# CPU-board-Sheet1-multi.net
KiCad netlist of a schematic drawn in Altium Designer
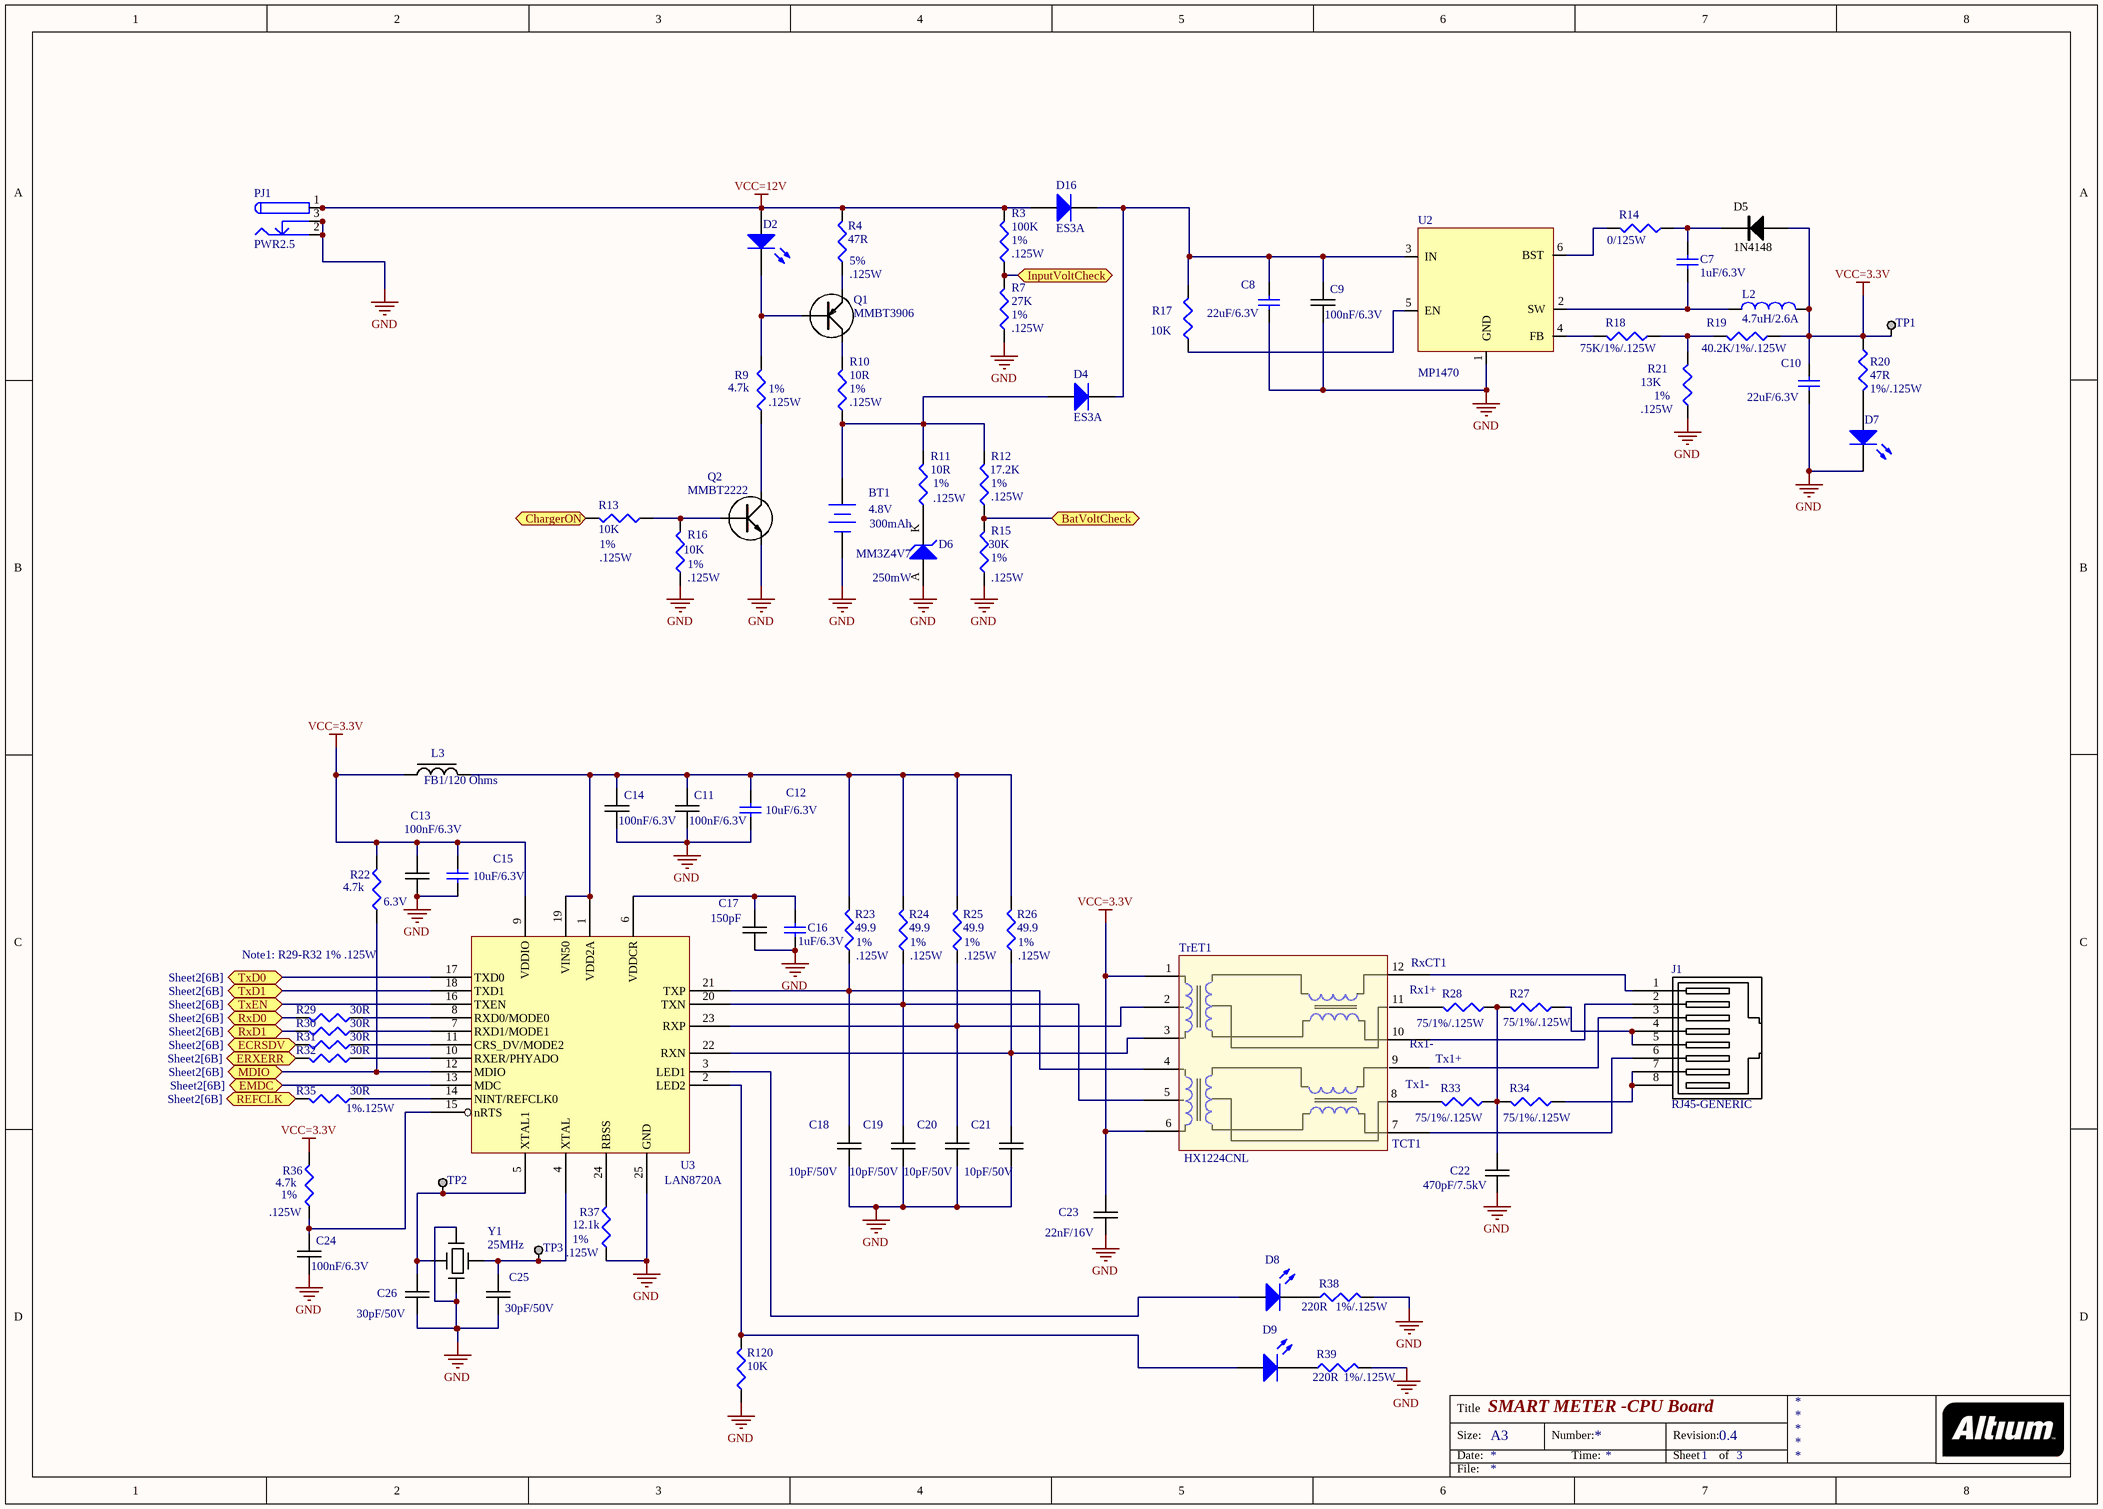
[diagram p0: CPU-board-Sheet1-multi.SchDoc]

(export (version "E")
  (design (tool "Eeschema 10.0.6"))
  (components
    (comp (ref "BT1")
      (value "4.8V")
      (footprint "BAT-2")
      (description "Multicell Battery")
      (fields
        (field (name "MANUFACTURER") "Guangdong, China (Mainland)")
        (field (name "PUBLISHER") "sunbangpower.en.alibaba.com")
      )
      (libsource (lib "Miscellaneous Devices") (part "Battery"))
    )
    (comp (ref "C7")
      (value "1uF/6.3V")
      (footprint "0402C-GENERIC")
      (description "Capacitor")
      (fields (field (name "MANUFACTURER") "Murata") (field (name "PUBLISHER") "Altium Limited"))
      (libsource (lib "Miscellaneous Devices") (part "Cap"))
    )
    (comp (ref "C8")
      (value "22uF/6.3V")
      (footprint "1206C-GENERIC")
      (description "Capacitor")
      (fields (field (name "MANUFACTURER") "Murata") (field (name "PUBLISHER") "Altium Limited"))
      (libsource (lib "Miscellaneous Devices") (part "Cap"))
    )
    (comp (ref "C9")
      (value "100nF/6.3V")
      (footprint "0402C-GENERIC")
      (description "CAPACITOR 0805 CERAMIC")
      (fields (field (name "MANUFACTURER") "Taiyo Yuden"))
      (libsource (lib "vh_altium_library") (part "0805C-18PF-50V-C0G-JOH"))
    )
    (comp (ref "C10")
      (value "22uF/6.3V")
      (footprint "1206C-GENERIC")
      (description "Capacitor")
      (fields (field (name "MANUFACTURER") "Murata") (field (name "PUBLISHER") "Altium Limited"))
      (libsource (lib "Miscellaneous Devices") (part "Cap"))
    )
    (comp (ref "C11")
      (value "100nF/6.3V")
      (footprint "0402C-GENERIC")
      (description "CAPACITOR 0805 CERAMIC")
      (fields (field (name "MANUFACTURER") "Taiyo Yuden"))
      (libsource (lib "vh_altium_library") (part "0805C-18PF-50V-C0G-JOH"))
    )
    (comp (ref "C12")
      (value "10uF/6.3V")
      (footprint "0402C-GENERIC")
      (description "Capacitor")
      (fields (field (name "MANUFACTURER") "Murata") (field (name "PUBLISHER") "Altium Limited"))
      (libsource (lib "Miscellaneous Devices") (part "Cap"))
    )
    (comp (ref "C13")
      (value "100nF/6.3V")
      (footprint "0402C-GENERIC")
      (description "CAPACITOR 0805 CERAMIC")
      (fields (field (name "MANUFACTURER") "Taiyo Yuden"))
      (libsource (lib "vh_altium_library") (part "0805C-18PF-50V-C0G-JOH"))
    )
    (comp (ref "C14")
      (value "100nF/6.3V")
      (footprint "0402C-GENERIC")
      (description "CAPACITOR 0805 CERAMIC")
      (fields (field (name "MANUFACTURER") "Taiyo Yuden"))
      (libsource (lib "vh_altium_library") (part "0805C-18PF-50V-C0G-JOH"))
    )
    (comp (ref "C15")
      (value "10uF/6.3V")
      (footprint "0402C-GENERIC")
      (description "Capacitor")
      (fields (field (name "MANUFACTURER") "Murata") (field (name "PUBLISHER") "Altium Limited"))
      (libsource (lib "Miscellaneous Devices") (part "Cap"))
    )
    (comp (ref "C16")
      (value "1uF/6.3V")
      (footprint "0402C-GENERIC")
      (description "Capacitor")
      (fields (field (name "MANUFACTURER") "Murata") (field (name "PUBLISHER") "Altium Limited"))
      (libsource (lib "Miscellaneous Devices") (part "Cap"))
    )
    (comp (ref "C17")
      (value "150pF")
      (footprint "0402C-GENERIC")
      (description "CAPACITOR 0805 CERAMIC")
      (fields (field (name "MANUFACTURER") "Wurth Electronics"))
      (libsource (lib "vh_altium_library") (part "0805C-18PF-50V-C0G-JOH"))
    )
    (comp (ref "C18")
      (value "10pF/50V")
      (footprint "0402C-GENERIC")
      (description "CAPACITOR 0805 CERAMIC")
      (fields (field (name "MANUFACTURER") "Murata"))
      (libsource (lib "vh_altium_library") (part "0805C-18PF-50V-C0G-JOH"))
    )
    (comp (ref "C19")
      (value "10pF/50V")
      (footprint "0402C-GENERIC")
      (description "CAPACITOR 0805 CERAMIC")
      (fields (field (name "MANUFACTURER") "Murata"))
      (libsource (lib "vh_altium_library") (part "0805C-18PF-50V-C0G-JOH"))
    )
    (comp (ref "C20")
      (value "10pF/50V")
      (footprint "0402C-GENERIC")
      (description "CAPACITOR 0805 CERAMIC")
      (fields (field (name "MANUFACTURER") "Murata"))
      (libsource (lib "vh_altium_library") (part "0805C-18PF-50V-C0G-JOH"))
    )
    (comp (ref "C21")
      (value "10pF/50V")
      (footprint "0402C-GENERIC")
      (description "CAPACITOR 0805 CERAMIC")
      (fields (field (name "MANUFACTURER") "Murata"))
      (libsource (lib "vh_altium_library") (part "0805C-18PF-50V-C0G-JOH"))
    )
    (comp (ref "C22")
      (value "470pF/7.5kV")
      (footprint "1808")
      (description "CAPACITOR 1808CERAMIC")
      (fields (field (name "MANUFACTURER") "Murata"))
      (libsource (lib "vh_altium_library") (part "0805C-18PF-50V-C0G-JOH"))
    )
    (comp (ref "C23")
      (value "22nF/16V")
      (footprint "0402C-GENERIC")
      (description "CAPACITOR 0805 CERAMIC")
      (fields (field (name "MANUFACTURER") "Murata Electronics"))
      (libsource (lib "vh_altium_library") (part "0805C-18PF-50V-C0G-JOH"))
    )
    (comp (ref "C24")
      (value "100nF/6.3V")
      (footprint "0402C-GENERIC")
      (description "CAPACITOR 0805 CERAMIC")
      (fields (field (name "MANUFACTURER") "Taiyo Yuden"))
      (libsource (lib "vh_altium_library") (part "0805C-18PF-50V-C0G-JOH"))
    )
    (comp (ref "C25")
      (value "30pF/50V")
      (footprint "0402C-GENERIC")
      (description "CAPACITOR 0805 CERAMIC")
      (fields (field (name "MANUFACTURER") "Murata"))
      (libsource (lib "vh_altium_library") (part "0805C-18PF-50V-C0G-JOH"))
    )
    (comp (ref "C26")
      (value "30pF/50V")
      (footprint "0402C-GENERIC")
      (description "CAPACITOR 0805 CERAMIC")
      (fields (field (name "MANUFACTURER") "Murata"))
      (libsource (lib "vh_altium_library") (part "0805C-18PF-50V-C0G-JOH"))
    )
    (comp (ref "D2")
      (value "LED2")
      (footprint "LED-SM")
      (description "Typical RED, GREEN, YELLOW, AMBER GaAs LED")
      (fields (field (name "MANUFACTURER") "Lite-On Inc") (field (name "PUBLISHER") "Altium Limited"))
      (libsource (lib "Miscellaneous Devices") (part "LED2"))
    )
    (comp (ref "D4")
      (value "ES3A")
      (footprint "DO214AA")
      (description "1 Amp General Purpose Rectifier")
      (fields (field (name "MANUFACTURER") "Fairchild Co") (field (name "PUBLISHER") "Altium Limited"))
      (libsource (lib "Miscellaneous Devices") (part "Diode 1N4007"))
    )
    (comp (ref "D5")
      (value "1N4148")
      (footprint "SOD-123")
      (description "1N4001")
      (fields (field (name "MANUFACTURER") "Vishay"))
      (libsource (lib "vh_altium_library") (part "1N4001"))
    )
    (comp (ref "D6")
      (value "MM3Z4V7")
      (footprint "SOT23-DIODE")
      (description "Zener Diode")
      (fields (field (name "MANUFACTURER") "Fairchild Semi") (field (name "PUBLISHER") "Altium Limited"))
      (libsource (lib "Miscellaneous Devices") (part "D Zener"))
    )
    (comp (ref "D7")
      (value "LED2")
      (footprint "LED-SM")
      (description "Typical RED, GREEN, YELLOW, AMBER GaAs LED")
      (fields (field (name "MANUFACTURER") "Lite-On Inc") (field (name "PUBLISHER") "Altium Limited"))
      (libsource (lib "Miscellaneous Devices") (part "LED2"))
    )
    (comp (ref "D8")
      (value "LED2")
      (footprint "LED-SM")
      (description "Typical RED, GREEN, YELLOW, AMBER GaAs LED")
      (fields (field (name "MANUFACTURER") "Lite-On Inc") (field (name "PUBLISHER") "Altium Limited"))
      (libsource (lib "Miscellaneous Devices") (part "LED2"))
    )
    (comp (ref "D9")
      (value "LED2")
      (footprint "LED-SM")
      (description "Typical RED, GREEN, YELLOW, AMBER GaAs LED")
      (fields (field (name "MANUFACTURER") "Lite-On Inc") (field (name "PUBLISHER") "Altium Limited"))
      (libsource (lib "Miscellaneous Devices") (part "LED2"))
    )
    (comp (ref "D16")
      (value "ES3A")
      (footprint "DO214AA")
      (description "1 Amp General Purpose Rectifier")
      (fields (field (name "MANUFACTURER") "Fairchild Co") (field (name "PUBLISHER") "Altium Limited"))
      (libsource (lib "Miscellaneous Devices") (part "Diode 1N4007"))
    )
    (comp (ref "J1")
      (value "RJ45-GENERIC")
      (footprint "RJ45-8/8")
      (description "GENERIC RJ45 CONNECTOR 8 PIN")
      (fields (field (name "MANUFACTURER") "Assman WSW Components"))
      (libsource (lib "vh_altium_library") (part "RJ45-GENERIC"))
    )
    (comp (ref "L2")
      (value "4.7uH/2.6A")
      (footprint "Inductor 4.7/6.8")
      (description "Inductor")
      (fields (field (name "MANUFACTURER") "Bourns") (field (name "PUBLISHER") "Altium Limited"))
      (libsource (lib "Miscellaneous Devices") (part "Inductor"))
    )
    (comp (ref "L3")
      (value "FB1/120 Ohms")
      (footprint "0603C-2U2")
      (description "1239AS-H-1R0N")
      (fields (field (name "MANUFACTURER") "Murata Electronics"))
      (libsource (lib "SMD Magnetics-SM") (part "1U-1239AS-TOKO"))
    )
    (comp (ref "PJ1")
      (value "PWR2.5")
      (footprint "Female Plug")
      (description "Low Voltage Power Supply Connector")
      (fields (field (name "MANUFACTURER") "CUI Inc") (field (name "PUBLISHER") "Altium Limited"))
      (libsource (lib "Miscellaneous Connectors") (part "PWR2.5"))
    )
    (comp (ref "Q1")
      (value "MMBT3906")
      (footprint "SOT23-BCE")
      (description "GENERIC PNP BIPOLAR TRANSISTOR")
      (fields (field (name "MANUFACTURER") "On Semi"))
      (libsource (lib "generic") (part "PNP-GENERIC"))
    )
    (comp (ref "Q2")
      (value "MMBT2222")
      (footprint "MMBT2222")
      (description "BC847 SMALL SIGNAL NPN TRANSISTOR")
      (fields (field (name "MANUFACTURER") "Diodes  Inc."))
      (libsource (lib "vh_altium_library") (part "MMBT2222"))
    )
    (comp (ref "R3")
      (value "100K")
      (footprint "0402R-TBD")
      (description "Resistor")
      (fields (field (name "MANUFACTURER") "Panasonic") (field (name "PUBLISHER") "Altium Limited"))
      (libsource (lib "Miscellaneous Devices") (part "Res3"))
    )
    (comp (ref "R4")
      (value "47R")
      (footprint "0402R-TBD")
      (description "Resistor")
      (fields (field (name "PUBLISHER") "Altium Limited"))
      (libsource (lib "Miscellaneous Devices") (part "Res3"))
    )
    (comp (ref "R7")
      (value "27K")
      (footprint "0402R-TBD")
      (description "Resistor")
      (fields (field (name "MANUFACTURER") "Panasonic") (field (name "PUBLISHER") "Altium Limited"))
      (libsource (lib "Miscellaneous Devices") (part "Res3"))
    )
    (comp (ref "R9")
      (value "4.7k")
      (footprint "0402R-TBD")
      (description "Resistor")
      (fields (field (name "MANUFACTURER") "Panasonic") (field (name "PUBLISHER") "Altium Limited"))
      (libsource (lib "Miscellaneous Devices") (part "Res3"))
    )
    (comp (ref "R10")
      (value "10R")
      (footprint "0402R-TBD")
      (description "Resistor")
      (fields (field (name "MANUFACTURER") "Panasonic") (field (name "PUBLISHER") "Altium Limited"))
      (libsource (lib "Miscellaneous Devices") (part "Res3"))
    )
    (comp (ref "R11")
      (value "10R")
      (footprint "0402R-TBD")
      (description "Resistor")
      (fields (field (name "MANUFACTURER") "Panasonic") (field (name "PUBLISHER") "Altium Limited"))
      (libsource (lib "Miscellaneous Devices") (part "Res3"))
    )
    (comp (ref "R12")
      (value "17.2K")
      (footprint "0402R-TBD")
      (description "Resistor")
      (fields (field (name "MANUFACTURER") "Vishay Dale") (field (name "PUBLISHER") "Altium Limited"))
      (libsource (lib "Miscellaneous Devices") (part "Res3"))
    )
    (comp (ref "R13")
      (value "10K")
      (footprint "0402R-TBD")
      (description "Resistor")
      (fields (field (name "MANUFACTURER") "Panasonic") (field (name "PUBLISHER") "Altium Limited"))
      (libsource (lib "Miscellaneous Devices") (part "Res3"))
    )
    (comp (ref "R14")
      (value "0/125W")
      (footprint "0402C-GENERIC")
      (description "Resistor")
      (fields (field (name "MANUFACTURER") "Vishay Dale") (field (name "PUBLISHER") "Altium Limited"))
      (libsource (lib "Miscellaneous Devices") (part "Res3"))
    )
    (comp (ref "R15")
      (value "30K")
      (footprint "0402R-TBD")
      (description "Resistor")
      (fields (field (name "MANUFACTURER") "Panasonic") (field (name "PUBLISHER") "Altium Limited"))
      (libsource (lib "Miscellaneous Devices") (part "Res3"))
    )
    (comp (ref "R16")
      (value "10K")
      (footprint "0402R-TBD")
      (description "Resistor")
      (fields (field (name "MANUFACTURER") "Panasonic") (field (name "PUBLISHER") "Altium Limited"))
      (libsource (lib "Miscellaneous Devices") (part "Res3"))
    )
    (comp (ref "R17")
      (value "10K")
      (footprint "0402R-TBD")
      (description "Resistor")
      (fields (field (name "MANUFACTURER") "Panasonic") (field (name "PUBLISHER") "Altium Limited"))
      (libsource (lib "Miscellaneous Devices") (part "Res3"))
    )
    (comp (ref "R18")
      (value "75K/1%/.125W")
      (footprint "0402C-TBD")
      (description "Resistor")
      (fields (field (name "MANUFACTURER") "Panasonic") (field (name "PUBLISHER") "Altium Limited"))
      (libsource (lib "Miscellaneous Devices") (part "Res3"))
    )
    (comp (ref "R19")
      (value "40.2K/1%/.125W")
      (footprint "0402R-TBD")
      (description "Resistor")
      (fields (field (name "MANUFACTURER") "Panasonic") (field (name "PUBLISHER") "Altium Limited"))
      (libsource (lib "Miscellaneous Devices") (part "Res3"))
    )
    (comp (ref "R20")
      (value "47R")
      (footprint "0402R-TBD")
      (description "Resistor")
      (fields (field (name "PUBLISHER") "Altium Limited"))
      (libsource (lib "Miscellaneous Devices") (part "Res3"))
    )
    (comp (ref "R21")
      (value "13K")
      (footprint "0402R-TBD")
      (description "Resistor")
      (fields (field (name "MANUFACTURER") "Panasonic") (field (name "PUBLISHER") "Altium Limited"))
      (libsource (lib "Miscellaneous Devices") (part "Res3"))
    )
    (comp (ref "R22")
      (value "4.7k")
      (footprint "0402R-TBD")
      (description "Resistor")
      (fields (field (name "MANUFACTURER") "Panasonic") (field (name "PUBLISHER") "Altium Limited"))
      (libsource (lib "Miscellaneous Devices") (part "Res3"))
    )
    (comp (ref "R23")
      (value "49.9")
      (footprint "0402R-TBD")
      (description "Resistor")
      (fields (field (name "MANUFACTURER") "Panasonic") (field (name "PUBLISHER") "Altium Limited"))
      (libsource (lib "Miscellaneous Devices") (part "Res3"))
    )
    (comp (ref "R24")
      (value "49.9")
      (footprint "0402R-TBD")
      (description "Resistor")
      (fields (field (name "MANUFACTURER") "Panasonic") (field (name "PUBLISHER") "Altium Limited"))
      (libsource (lib "Miscellaneous Devices") (part "Res3"))
    )
    (comp (ref "R25")
      (value "49.9")
      (footprint "0402R-TBD")
      (description "Resistor")
      (fields (field (name "MANUFACTURER") "Panasonic") (field (name "PUBLISHER") "Altium Limited"))
      (libsource (lib "Miscellaneous Devices") (part "Res3"))
    )
    (comp (ref "R26")
      (value "49.9")
      (footprint "0402R-TBD")
      (description "Resistor")
      (fields (field (name "MANUFACTURER") "Panasonic") (field (name "PUBLISHER") "Altium Limited"))
      (libsource (lib "Miscellaneous Devices") (part "Res3"))
    )
    (comp (ref "R27")
      (value "75/1%/.125W")
      (footprint "0402R-TBD")
      (description "Resistor")
      (fields (field (name "MANUFACTURER") "Panasonic") (field (name "PUBLISHER") "Altium Limited"))
      (libsource (lib "Miscellaneous Devices") (part "Res3"))
    )
    (comp (ref "R28")
      (value "75/1%/.125W")
      (footprint "0402R-TBD")
      (description "Resistor")
      (fields (field (name "MANUFACTURER") "Panasonic") (field (name "PUBLISHER") "Altium Limited"))
      (libsource (lib "Miscellaneous Devices") (part "Res3"))
    )
    (comp (ref "R29")
      (value "30R")
      (footprint "0402R-TBD")
      (description "Resistor")
      (fields (field (name "MANUFACTURER") "Panasonic") (field (name "PUBLISHER") "Altium Limited"))
      (libsource (lib "Miscellaneous Devices") (part "Res3"))
    )
    (comp (ref "R30")
      (value "30R")
      (footprint "0402R-TBD")
      (description "Resistor")
      (fields (field (name "MANUFACTURER") "Panasonic") (field (name "PUBLISHER") "Altium Limited"))
      (libsource (lib "Miscellaneous Devices") (part "Res3"))
    )
    (comp (ref "R31")
      (value "30R")
      (footprint "0402R-TBD")
      (description "Resistor")
      (fields (field (name "MANUFACTURER") "Panasonic") (field (name "PUBLISHER") "Altium Limited"))
      (libsource (lib "Miscellaneous Devices") (part "Res3"))
    )
    (comp (ref "R32")
      (value "30R")
      (footprint "0402R-TBD")
      (description "Resistor")
      (fields (field (name "MANUFACTURER") "Panasonic") (field (name "PUBLISHER") "Altium Limited"))
      (libsource (lib "Miscellaneous Devices") (part "Res3"))
    )
    (comp (ref "R33")
      (value "75/1%/.125W")
      (footprint "0402R-TBD")
      (description "Resistor")
      (fields (field (name "MANUFACTURER") "Panasonic") (field (name "PUBLISHER") "Altium Limited"))
      (libsource (lib "Miscellaneous Devices") (part "Res3"))
    )
    (comp (ref "R34")
      (value "75/1%/.125W")
      (footprint "0402R-TBD")
      (description "Resistor")
      (fields (field (name "MANUFACTURER") "Panasonic") (field (name "PUBLISHER") "Altium Limited"))
      (libsource (lib "Miscellaneous Devices") (part "Res3"))
    )
    (comp (ref "R35")
      (value "30R")
      (footprint "0402R-TBD")
      (description "Resistor")
      (fields (field (name "MANUFACTURER") "Panasonic") (field (name "PUBLISHER") "Altium Limited"))
      (libsource (lib "Miscellaneous Devices") (part "Res3"))
    )
    (comp (ref "R36")
      (value "4.7k")
      (footprint "0402R-TBD")
      (description "Resistor")
      (fields (field (name "MANUFACTURER") "Panasonic") (field (name "PUBLISHER") "Altium Limited"))
      (libsource (lib "Miscellaneous Devices") (part "Res3"))
    )
    (comp (ref "R37")
      (value "12.1k")
      (footprint "0402R-TBD")
      (description "Resistor")
      (fields (field (name "MANUFACTURER") "Panasonic") (field (name "PUBLISHER") "Altium Limited"))
      (libsource (lib "Miscellaneous Devices") (part "Res3"))
    )
    (comp (ref "R38")
      (value "220R")
      (footprint "0402R-TBD")
      (description "Resistor")
      (fields (field (name "MANUFACTURER") "Panasonic") (field (name "PUBLISHER") "Altium Limited"))
      (libsource (lib "Miscellaneous Devices") (part "Res3"))
    )
    (comp (ref "R39")
      (value "220R")
      (footprint "0402R-TBD")
      (description "Resistor")
      (fields (field (name "MANUFACTURER") "Panasonic") (field (name "PUBLISHER") "Altium Limited"))
      (libsource (lib "Miscellaneous Devices") (part "Res3"))
    )
    (comp (ref "R120")
      (value "10K")
      (footprint "0402R-TBD")
      (description "Resistor")
      (fields (field (name "MANUFACTURER") "Panasonic") (field (name "PUBLISHER") "Altium Limited"))
      (libsource (lib "Miscellaneous Devices") (part "Res3"))
    )
    (comp (ref "TP1")
      (value "TESTPOINT")
      (footprint "TESTPOINT")
      (description "TESTPOINT SCOPE GRABBER")
      (fields
        (field (name "MANUFACTURER PART NUMBER") "5010")
        (field (name "MANUFACTURER") "Keystone Electronics")
      )
      (libsource (lib "vh_altium_library") (part "TESTPOINT"))
    )
    (comp (ref "TP2")
      (value "TESTPOINT")
      (footprint "TESTPOINT")
      (description "TESTPOINT SCOPE GRABBER")
      (fields
        (field (name "MANUFACTURER PART NUMBER") "5010")
        (field (name "MANUFACTURER") "Keystone Electronics")
      )
      (libsource (lib "vh_altium_library") (part "TESTPOINT"))
    )
    (comp (ref "TP3")
      (value "TESTPOINT")
      (footprint "TESTPOINT")
      (description "TESTPOINT SCOPE GRABBER")
      (fields
        (field (name "MANUFACTURER PART NUMBER") "5010")
        (field (name "MANUFACTURER") "Keystone Electronics")
      )
      (libsource (lib "vh_altium_library") (part "TESTPOINT"))
    )
    (comp (ref "TrET1")
      (value "HX1224CNL")
      (footprint "HX1224-NL")
      (fields (field (name "MANUFACTURER") "Pulse Electronic Corporation"))
      (libsource (lib "SMLib") (part "hx1224nl"))
    )
    (comp (ref "U2")
      (value "MP1470")
      (footprint "MP1470")
      (fields (field (name "MANUFACTURER") "MPS Inc"))
      (libsource (lib "SMLib") (part "MP1470"))
    )
    (comp (ref "U3")
      (value "LAN8720A")
      (footprint "Atmel Multimedia:QFN24_4X4_N")
      (fields (field (name "MANUFACTURER") "Microchip"))
      (libsource (lib "SMLib") (part "LAN8720"))
    )
    (comp (ref "Y1")
      (value "25MHz")
      (footprint "CeramicResonator8-16MHZ")
      (description "25MHz CRYSTAL HC49US SHORT BODY")
      (fields (field (name "MANUFACTURER") "KDS DAISHINKU.Corp"))
      (libsource (lib "Crystals") (part "12MC-HC49US-7MM"))
    )
  )
  (nets
    (net (code "1") (name "/BatVoltCheck") (class "Default")
      (node (ref "R12") (pin "1") (pinfunction "1_1") (pintype "passive"))
      (node (ref "R15") (pin "2") (pinfunction "2_2") (pintype "passive"))
    )
    (net (code "2") (name "/ChargerON") (class "Default")
      (node (ref "R13") (pin "2") (pinfunction "2_2") (pintype "passive"))
    )
    (net (code "3") (name "/ECRSDV") (class "Default")
      (node (ref "R31") (pin "2") (pinfunction "2_2") (pintype "passive"))
    )
    (net (code "4") (name "/EMDC") (class "Default")
      (node (ref "U3") (pin "13") (pinfunction "MDC_13") (pintype "passive"))
    )
    (net (code "5") (name "/ERXERR") (class "Default")
      (node (ref "R32") (pin "2") (pinfunction "2_2") (pintype "passive"))
    )
    (net (code "6") (name "/InputVoltCheck") (class "Default")
      (node (ref "R3") (pin "1") (pinfunction "1_1") (pintype "passive"))
      (node (ref "R7") (pin "2") (pinfunction "2_2") (pintype "passive"))
    )
    (net (code "7") (name "/MDIO") (class "Default")
      (node (ref "R22") (pin "1") (pinfunction "1_1") (pintype "passive"))
      (node (ref "U3") (pin "12") (pinfunction "MDIO_12") (pintype "passive"))
    )
    (net (code "8") (name "/REFCLK") (class "Default")
      (node (ref "R35") (pin "2") (pinfunction "2_2") (pintype "passive"))
    )
    (net (code "9") (name "/RxD0") (class "Default")
      (node (ref "R29") (pin "2") (pinfunction "2_2") (pintype "passive"))
    )
    (net (code "10") (name "/RxD1") (class "Default")
      (node (ref "R30") (pin "2") (pinfunction "2_2") (pintype "passive"))
    )
    (net (code "11") (name "/TxD0") (class "Default")
      (node (ref "U3") (pin "17") (pinfunction "TXD0_17") (pintype "passive"))
    )
    (net (code "12") (name "/TxD1") (class "Default")
      (node (ref "U3") (pin "18") (pinfunction "TXD1_18") (pintype "passive"))
    )
    (net (code "13") (name "/TxEN") (class "Default")
      (node (ref "U3") (pin "16") (pinfunction "TXEN_16") (pintype "passive"))
    )
    (net (code "14") (name "GND") (class "Default")
      (node (ref "BT1") (pin "2") (pinfunction "-_2") (pintype "passive"))
      (node (ref "C10") (pin "2") (pinfunction "2_2") (pintype "passive"))
      (node (ref "C11") (pin "2") (pintype "passive"))
      (node (ref "C12") (pin "2") (pinfunction "2_2") (pintype "passive"))
      (node (ref "C13") (pin "2") (pintype "passive"))
      (node (ref "C14") (pin "2") (pintype "passive"))
      (node (ref "C15") (pin "2") (pinfunction "2_2") (pintype "passive"))
      (node (ref "C16") (pin "1") (pinfunction "1_1") (pintype "passive"))
      (node (ref "C17") (pin "2") (pintype "passive"))
      (node (ref "C18") (pin "2") (pintype "passive"))
      (node (ref "C19") (pin "2") (pintype "passive"))
      (node (ref "C20") (pin "2") (pintype "passive"))
      (node (ref "C21") (pin "2") (pintype "passive"))
      (node (ref "C22") (pin "2") (pintype "passive"))
      (node (ref "C23") (pin "2") (pintype "passive"))
      (node (ref "C24") (pin "2") (pintype "passive"))
      (node (ref "C25") (pin "2") (pintype "passive"))
      (node (ref "C26") (pin "2") (pintype "passive"))
      (node (ref "C8") (pin "2") (pinfunction "2_2") (pintype "passive"))
      (node (ref "C9") (pin "2") (pintype "passive"))
      (node (ref "D6") (pin "A") (pinfunction "A_A") (pintype "passive"))
      (node (ref "D7") (pin "2") (pinfunction "K_2") (pintype "passive"))
      (node (ref "PJ1") (pin "2") (pinfunction "2_2") (pintype "power_in"))
      (node (ref "PJ1") (pin "2A") (pinfunction "2A_2A") (pintype "power_in"))
      (node (ref "PJ1") (pin "2B") (pinfunction "2B_2B") (pintype "power_in"))
      (node (ref "PJ1") (pin "3") (pinfunction "3_3") (pintype "power_in"))
      (node (ref "PJ1") (pin "3A") (pinfunction "3A_3A") (pintype "power_in"))
      (node (ref "PJ1") (pin "3B") (pinfunction "3B_3B") (pintype "power_in"))
      (node (ref "Q2") (pin "E") (pintype "passive"))
      (node (ref "R120") (pin "1") (pinfunction "1_1") (pintype "passive"))
      (node (ref "R15") (pin "1") (pinfunction "1_1") (pintype "passive"))
      (node (ref "R16") (pin "1") (pinfunction "1_1") (pintype "passive"))
      (node (ref "R21") (pin "1") (pinfunction "1_1") (pintype "passive"))
      (node (ref "R37") (pin "1") (pinfunction "1_1") (pintype "passive"))
      (node (ref "R38") (pin "2") (pinfunction "2_2") (pintype "passive"))
      (node (ref "R39") (pin "2") (pinfunction "2_2") (pintype "passive"))
      (node (ref "R7") (pin "1") (pinfunction "1_1") (pintype "passive"))
      (node (ref "U2") (pin "1") (pinfunction "GND_1") (pintype "passive"))
      (node (ref "U3") (pin "25") (pinfunction "GND_25") (pintype "passive"))
      (node (ref "Y1") (pin "2") (pintype "passive"))
      (node (ref "Y1") (pin "4") (pintype "passive"))
    )
    (net (code "15") (name "Net-(BT1-+)") (class "Default")
      (node (ref "BT1") (pin "1") (pinfunction "+_1") (pintype "passive"))
      (node (ref "D4") (pin "1") (pinfunction "A_1") (pintype "passive"))
      (node (ref "R10") (pin "1") (pinfunction "1_1") (pintype "passive"))
      (node (ref "R11") (pin "2") (pinfunction "2_2") (pintype "passive"))
      (node (ref "R12") (pin "2") (pinfunction "2_2") (pintype "passive"))
    )
    (net (code "16") (name "Net-(C7-Pad2)") (class "Default")
      (node (ref "C7") (pin "2") (pinfunction "2_2") (pintype "passive"))
      (node (ref "D5") (pin "K") (pinfunction "K_K") (pintype "passive"))
      (node (ref "R14") (pin "1") (pinfunction "1_1") (pintype "passive"))
    )
    (net (code "17") (name "Net-(C22-Pad1)") (class "Default")
      (node (ref "C22") (pin "1") (pintype "passive"))
      (node (ref "R27") (pin "2") (pinfunction "2_2") (pintype "passive"))
      (node (ref "R28") (pin "1") (pinfunction "1_1") (pintype "passive"))
      (node (ref "R33") (pin "1") (pinfunction "1_1") (pintype "passive"))
      (node (ref "R34") (pin "2") (pinfunction "2_2") (pintype "passive"))
    )
    (net (code "18") (name "Net-(D2-K)") (class "Default")
      (node (ref "D2") (pin "2") (pinfunction "K_2") (pintype "passive"))
      (node (ref "Q1") (pin "B") (pintype "passive"))
      (node (ref "R9") (pin "2") (pinfunction "2_2") (pintype "passive"))
    )
    (net (code "19") (name "Net-(D6-PadK)") (class "Default")
      (node (ref "D6") (pin "K") (pinfunction "K_K") (pintype "passive"))
      (node (ref "R11") (pin "1") (pinfunction "1_1") (pintype "passive"))
    )
    (net (code "20") (name "Net-(D7-A)") (class "Default")
      (node (ref "D7") (pin "1") (pinfunction "A_1") (pintype "passive"))
      (node (ref "R20") (pin "2") (pinfunction "2_2") (pintype "passive"))
    )
    (net (code "21") (name "Net-(D8-A)") (class "Default")
      (node (ref "D8") (pin "1") (pinfunction "A_1") (pintype "passive"))
      (node (ref "U3") (pin "3") (pinfunction "LED1_3") (pintype "passive"))
    )
    (net (code "22") (name "Net-(D8-K)") (class "Default")
      (node (ref "D8") (pin "2") (pinfunction "K_2") (pintype "passive"))
      (node (ref "R38") (pin "1") (pinfunction "1_1") (pintype "passive"))
    )
    (net (code "23") (name "Net-(D9-A)") (class "Default")
      (node (ref "D9") (pin "1") (pinfunction "A_1") (pintype "passive"))
      (node (ref "R120") (pin "2") (pinfunction "2_2") (pintype "passive"))
      (node (ref "U3") (pin "2") (pinfunction "LED2_2") (pintype "passive"))
    )
    (net (code "24") (name "Net-(D9-K)") (class "Default")
      (node (ref "D9") (pin "2") (pinfunction "K_2") (pintype "passive"))
      (node (ref "R39") (pin "1") (pinfunction "1_1") (pintype "passive"))
    )
    (net (code "25") (name "Net-(D16-K)") (class "Default")
      (node (ref "C8") (pin "1") (pinfunction "1_1") (pintype "passive"))
      (node (ref "C9") (pin "1") (pintype "passive"))
      (node (ref "D16") (pin "2") (pinfunction "K_2") (pintype "passive"))
      (node (ref "D4") (pin "2") (pinfunction "K_2") (pintype "passive"))
      (node (ref "R17") (pin "2") (pinfunction "2_2") (pintype "passive"))
      (node (ref "U2") (pin "3") (pinfunction "IN_3") (pintype "passive"))
    )
    (net (code "26") (name "Net-(J1-Pad1)") (class "Default")
      (node (ref "J1") (pin "1") (pintype "passive"))
      (node (ref "TrET1") (pin "12") (pinfunction "12_12") (pintype "passive"))
    )
    (net (code "27") (name "Net-(J1-Pad2)") (class "Default")
      (node (ref "J1") (pin "2") (pintype "passive"))
      (node (ref "TrET1") (pin "10") (pinfunction "10_10") (pintype "passive"))
    )
    (net (code "28") (name "Net-(J1-Pad3)") (class "Default")
      (node (ref "J1") (pin "3") (pintype "passive"))
      (node (ref "TrET1") (pin "9") (pinfunction "9_9") (pintype "passive"))
    )
    (net (code "29") (name "Net-(J1-Pad4)") (class "Default")
      (node (ref "J1") (pin "4") (pintype "passive"))
      (node (ref "J1") (pin "5") (pintype "passive"))
      (node (ref "R27") (pin "1") (pinfunction "1_1") (pintype "passive"))
    )
    (net (code "30") (name "Net-(J1-Pad6)") (class "Default")
      (node (ref "J1") (pin "6") (pintype "passive"))
      (node (ref "TrET1") (pin "7") (pinfunction "7_7") (pintype "passive"))
    )
    (net (code "31") (name "Net-(J1-Pad7)") (class "Default")
      (node (ref "J1") (pin "7") (pintype "passive"))
      (node (ref "J1") (pin "8") (pintype "passive"))
      (node (ref "R34") (pin "1") (pinfunction "1_1") (pintype "passive"))
    )
    (net (code "32") (name "Net-(Q1-PadC)") (class "Default")
      (node (ref "Q1") (pin "C") (pintype "passive"))
      (node (ref "R10") (pin "2") (pinfunction "2_2") (pintype "passive"))
    )
    (net (code "33") (name "Net-(Q1-PadE)") (class "Default")
      (node (ref "Q1") (pin "E") (pintype "passive"))
      (node (ref "R4") (pin "1") (pinfunction "1_1") (pintype "passive"))
    )
    (net (code "34") (name "Net-(Q2-PadB)") (class "Default")
      (node (ref "Q2") (pin "B") (pintype "passive"))
      (node (ref "R13") (pin "1") (pinfunction "1_1") (pintype "passive"))
      (node (ref "R16") (pin "2") (pinfunction "2_2") (pintype "passive"))
    )
    (net (code "35") (name "Net-(Q2-PadC)") (class "Default")
      (node (ref "Q2") (pin "C") (pintype "passive"))
      (node (ref "R9") (pin "1") (pinfunction "1_1") (pintype "passive"))
    )
    (net (code "36") (name "Net-(R18-Pad1)") (class "Default")
      (node (ref "R18") (pin "1") (pinfunction "1_1") (pintype "passive"))
      (node (ref "R19") (pin "2") (pinfunction "2_2") (pintype "passive"))
      (node (ref "R21") (pin "2") (pinfunction "2_2") (pintype "passive"))
    )
    (net (code "37") (name "Net-(R28-Pad2)") (class "Default")
      (node (ref "R28") (pin "2") (pinfunction "2_2") (pintype "passive"))
      (node (ref "TrET1") (pin "11") (pinfunction "11_11") (pintype "passive"))
    )
    (net (code "38") (name "Net-(R33-Pad2)") (class "Default")
      (node (ref "R33") (pin "2") (pinfunction "2_2") (pintype "passive"))
      (node (ref "TrET1") (pin "8") (pinfunction "8_8") (pintype "passive"))
    )
    (net (code "39") (name "Net-(TrET1-TD-)") (class "Default")
      (node (ref "C21") (pin "1") (pintype "passive"))
      (node (ref "R26") (pin "1") (pinfunction "1_1") (pintype "passive"))
      (node (ref "TrET1") (pin "3") (pinfunction "TD-_3") (pintype "passive"))
      (node (ref "U3") (pin "22") (pinfunction "RXN_22") (pintype "passive"))
    )
    (net (code "40") (name "Net-(TrET1-TDCT)") (class "Default")
      (node (ref "C20") (pin "1") (pintype "passive"))
      (node (ref "R25") (pin "1") (pinfunction "1_1") (pintype "passive"))
      (node (ref "TrET1") (pin "2") (pinfunction "TDCT_2") (pintype "passive"))
      (node (ref "U3") (pin "23") (pinfunction "RXP_23") (pintype "passive"))
    )
    (net (code "41") (name "Net-(U2-BST)") (class "Default")
      (node (ref "R14") (pin "2") (pinfunction "2_2") (pintype "passive"))
      (node (ref "U2") (pin "6") (pinfunction "BST_6") (pintype "passive"))
    )
    (net (code "42") (name "Net-(U2-EN)") (class "Default")
      (node (ref "R17") (pin "1") (pinfunction "1_1") (pintype "passive"))
      (node (ref "U2") (pin "5") (pinfunction "EN_5") (pintype "passive"))
    )
    (net (code "43") (name "Net-(U2-FB)") (class "Default")
      (node (ref "R18") (pin "2") (pinfunction "2_2") (pintype "passive"))
      (node (ref "U2") (pin "4") (pinfunction "FB_4") (pintype "passive"))
    )
    (net (code "44") (name "Net-(U2-SW)") (class "Default")
      (node (ref "C7") (pin "1") (pinfunction "1_1") (pintype "passive"))
      (node (ref "L2") (pin "1") (pinfunction "1_1") (pintype "passive"))
      (node (ref "U2") (pin "2") (pinfunction "SW_2") (pintype "passive"))
    )
    (net (code "45") (name "Net-(U3-CRS_DV{slash}MODE2)") (class "Default")
      (node (ref "R31") (pin "1") (pinfunction "1_1") (pintype "passive"))
      (node (ref "U3") (pin "11") (pinfunction "CRS_DV/MODE2_11") (pintype "passive"))
    )
    (net (code "46") (name "Net-(U3-NINT{slash}REFCLK0)") (class "Default")
      (node (ref "R35") (pin "1") (pinfunction "1_1") (pintype "passive"))
      (node (ref "U3") (pin "14") (pinfunction "NINT/REFCLK0_14") (pintype "passive"))
    )
    (net (code "47") (name "Net-(U3-RBSS)") (class "Default")
      (node (ref "R37") (pin "2") (pinfunction "2_2") (pintype "passive"))
      (node (ref "U3") (pin "24") (pinfunction "RBSS_24") (pintype "passive"))
    )
    (net (code "48") (name "Net-(U3-RXD0{slash}MODE0)") (class "Default")
      (node (ref "R29") (pin "1") (pinfunction "1_1") (pintype "passive"))
      (node (ref "U3") (pin "8") (pinfunction "RXD0/MODE0_8") (pintype "passive"))
    )
    (net (code "49") (name "Net-(U3-RXD1{slash}MODE1)") (class "Default")
      (node (ref "R30") (pin "1") (pinfunction "1_1") (pintype "passive"))
      (node (ref "U3") (pin "7") (pinfunction "RXD1/MODE1_7") (pintype "passive"))
    )
    (net (code "50") (name "Net-(U3-RXER{slash}PHYADO)") (class "Default")
      (node (ref "R32") (pin "1") (pinfunction "1_1") (pintype "passive"))
      (node (ref "U3") (pin "10") (pinfunction "RXER/PHYADO_10") (pintype "passive"))
    )
    (net (code "51") (name "Net-(U3-TXN)") (class "Default")
      (node (ref "C19") (pin "1") (pintype "passive"))
      (node (ref "R24") (pin "1") (pinfunction "1_1") (pintype "passive"))
      (node (ref "TrET1") (pin "5") (pinfunction "5_5") (pintype "passive"))
      (node (ref "U3") (pin "20") (pinfunction "TXN_20") (pintype "passive"))
    )
    (net (code "52") (name "Net-(U3-TXP)") (class "Default")
      (node (ref "C18") (pin "1") (pintype "passive"))
      (node (ref "R23") (pin "1") (pinfunction "1_1") (pintype "passive"))
      (node (ref "TrET1") (pin "4") (pinfunction "4_4") (pintype "passive"))
      (node (ref "U3") (pin "21") (pinfunction "TXP_21") (pintype "passive"))
    )
    (net (code "53") (name "Net-(U3-VDD2A)") (class "Default")
      (node (ref "C11") (pin "1") (pintype "passive"))
      (node (ref "C12") (pin "1") (pinfunction "1_1") (pintype "passive"))
      (node (ref "C14") (pin "1") (pintype "passive"))
      (node (ref "L3") (pin "2") (pinfunction "2_2") (pintype "passive"))
      (node (ref "R23") (pin "2") (pinfunction "2_2") (pintype "passive"))
      (node (ref "R24") (pin "2") (pinfunction "2_2") (pintype "passive"))
      (node (ref "R25") (pin "2") (pinfunction "2_2") (pintype "passive"))
      (node (ref "R26") (pin "2") (pinfunction "2_2") (pintype "passive"))
      (node (ref "U3") (pin "1") (pinfunction "VDD2A_1") (pintype "passive"))
      (node (ref "U3") (pin "19") (pinfunction "VIN50_19") (pintype "passive"))
    )
    (net (code "54") (name "Net-(U3-VDDCR)") (class "Default")
      (node (ref "C16") (pin "2") (pinfunction "2_2") (pintype "passive"))
      (node (ref "C17") (pin "1") (pintype "passive"))
      (node (ref "U3") (pin "6") (pinfunction "VDDCR_6") (pintype "passive"))
    )
    (net (code "55") (name "Net-(U3-XTAL)") (class "Default")
      (node (ref "C25") (pin "1") (pintype "passive"))
      (node (ref "TP3") (pin "1") (pinfunction "1_1") (pintype "passive"))
      (node (ref "U3") (pin "4") (pinfunction "XTAL_4") (pintype "passive"))
      (node (ref "Y1") (pin "1") (pintype "passive"))
    )
    (net (code "56") (name "Net-(U3-XTAL1)") (class "Default")
      (node (ref "C26") (pin "1") (pintype "passive"))
      (node (ref "TP2") (pin "1") (pinfunction "1_1") (pintype "passive"))
      (node (ref "U3") (pin "5") (pinfunction "XTAL1_5") (pintype "passive"))
      (node (ref "Y1") (pin "3") (pintype "passive"))
    )
    (net (code "57") (name "Net-(U3-nRTS)") (class "Default")
      (node (ref "C24") (pin "1") (pintype "passive"))
      (node (ref "R36") (pin "1") (pinfunction "1_1") (pintype "passive"))
      (node (ref "U3") (pin "15") (pinfunction "nRTS_15") (pintype "passive"))
    )
    (net (code "58") (name "VCC=3.3V") (class "Default")
      (node (ref "C10") (pin "1") (pinfunction "1_1") (pintype "passive"))
      (node (ref "C13") (pin "1") (pintype "passive"))
      (node (ref "C15") (pin "1") (pinfunction "1_1") (pintype "passive"))
      (node (ref "C23") (pin "1") (pintype "passive"))
      (node (ref "D5") (pin "A") (pinfunction "A_A") (pintype "passive"))
      (node (ref "L2") (pin "2") (pinfunction "2_2") (pintype "passive"))
      (node (ref "L3") (pin "1") (pinfunction "1_1") (pintype "passive"))
      (node (ref "R19") (pin "1") (pinfunction "1_1") (pintype "passive"))
      (node (ref "R20") (pin "1") (pinfunction "1_1") (pintype "passive"))
      (node (ref "R22") (pin "2") (pinfunction "2_2") (pintype "passive"))
      (node (ref "R36") (pin "2") (pinfunction "2_2") (pintype "passive"))
      (node (ref "TP1") (pin "1") (pinfunction "1_1") (pintype "passive"))
      (node (ref "TrET1") (pin "1") (pinfunction "TD+_1") (pintype "passive"))
      (node (ref "TrET1") (pin "6") (pinfunction "6_6") (pintype "passive"))
      (node (ref "U3") (pin "9") (pinfunction "VDDIO_9") (pintype "passive"))
    )
    (net (code "59") (name "VCC=12V") (class "Default")
      (node (ref "D16") (pin "1") (pinfunction "A_1") (pintype "passive"))
      (node (ref "D2") (pin "1") (pinfunction "A_1") (pintype "passive"))
      (node (ref "PJ1") (pin "1") (pinfunction "1_1") (pintype "power_in"))
      (node (ref "PJ1") (pin "1A") (pinfunction "1A_1A") (pintype "power_in"))
      (node (ref "PJ1") (pin "1B") (pinfunction "1B_1B") (pintype "power_in"))
      (node (ref "R3") (pin "2") (pinfunction "2_2") (pintype "passive"))
      (node (ref "R4") (pin "2") (pinfunction "2_2") (pintype "passive"))
    )
  )
)
